# lpcdev.net
KiCad netlist of a schematic drawn in EAGLE
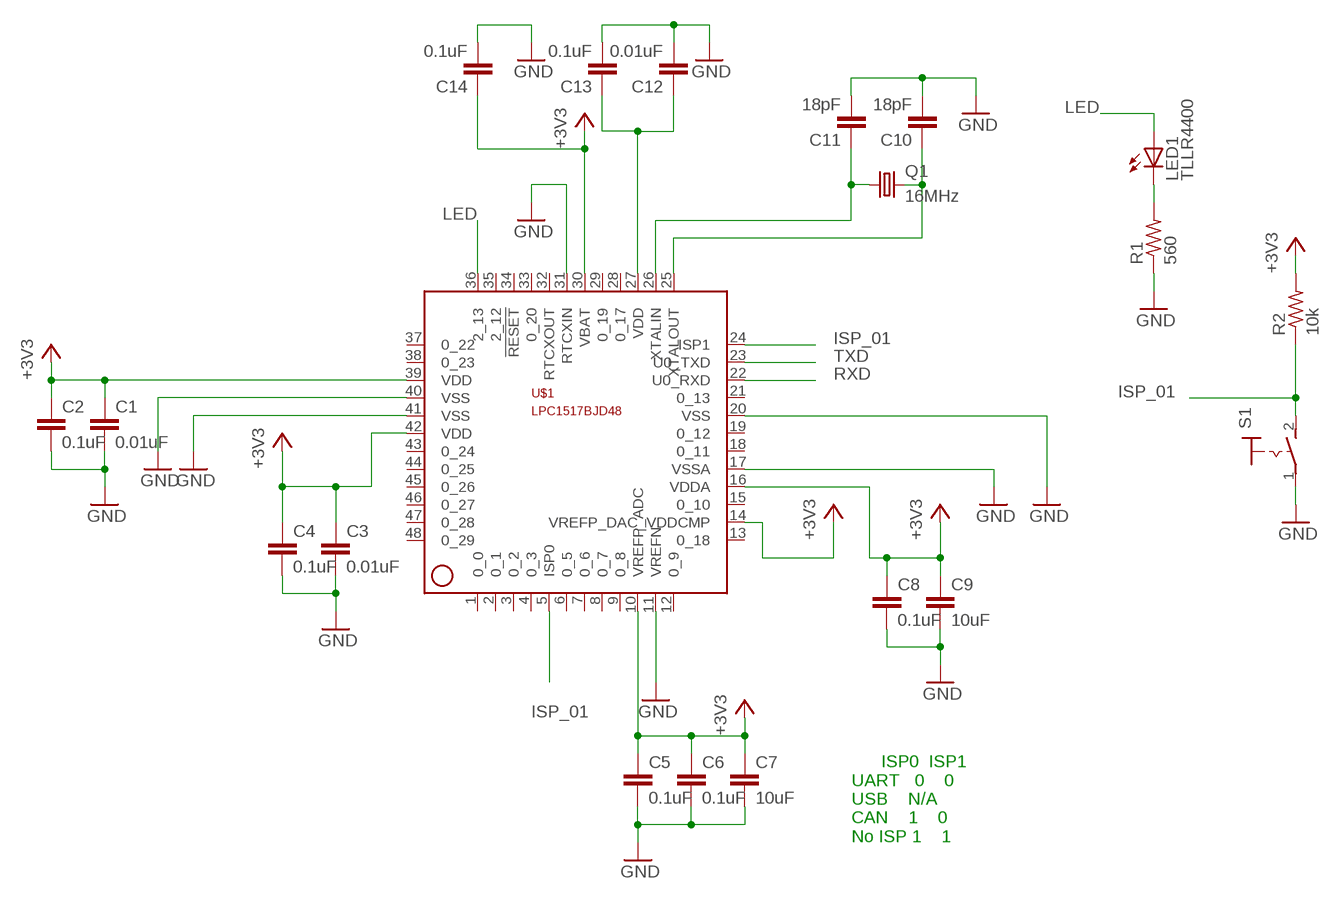
[diagram p0: schematic, sheet 1]

(export (version "E")
  (design (tool "Eeschema 10.0.6"))
  (components
    (comp (ref "C1")
      (value "0.01uF")
      (footprint "eagle-import:C0805")
      (libsource (lib "eagle-import") (part "C-EUC0805"))
    )
    (comp (ref "C2")
      (value "0.1uF")
      (footprint "eagle-import:C0805")
      (libsource (lib "eagle-import") (part "C-EUC0805"))
    )
    (comp (ref "C3")
      (value "0.01uF")
      (footprint "eagle-import:C0805")
      (libsource (lib "eagle-import") (part "C-EUC0805"))
    )
    (comp (ref "C4")
      (value "0.1uF")
      (footprint "eagle-import:C0805")
      (libsource (lib "eagle-import") (part "C-EUC0805"))
    )
    (comp (ref "C5")
      (value "0.1uF")
      (footprint "eagle-import:C0805")
      (libsource (lib "eagle-import") (part "C-EUC0805"))
    )
    (comp (ref "C6")
      (value "0.1uF")
      (footprint "eagle-import:C0805")
      (libsource (lib "eagle-import") (part "C-EUC0805"))
    )
    (comp (ref "C7")
      (value "10uF")
      (footprint "eagle-import:C0805")
      (libsource (lib "eagle-import") (part "C-EUC0805"))
    )
    (comp (ref "C8")
      (value "0.1uF")
      (footprint "eagle-import:C0805")
      (libsource (lib "eagle-import") (part "C-EUC0805"))
    )
    (comp (ref "C9")
      (value "10uF")
      (footprint "eagle-import:C0805")
      (libsource (lib "eagle-import") (part "C-EUC0805"))
    )
    (comp (ref "C10")
      (value "18pF")
      (footprint "eagle-import:C0805")
      (libsource (lib "eagle-import") (part "C-EUC0805"))
    )
    (comp (ref "C11")
      (value "18pF")
      (footprint "eagle-import:C0805")
      (libsource (lib "eagle-import") (part "C-EUC0805"))
    )
    (comp (ref "C12")
      (value "0.01uF")
      (footprint "eagle-import:C0805")
      (libsource (lib "eagle-import") (part "C-EUC0805"))
    )
    (comp (ref "C13")
      (value "0.1uF")
      (footprint "eagle-import:C0805")
      (libsource (lib "eagle-import") (part "C-EUC0805"))
    )
    (comp (ref "C14")
      (value "0.1uF")
      (footprint "eagle-import:C0805")
      (libsource (lib "eagle-import") (part "C-EUC0805"))
    )
    (comp (ref "LED1")
      (value "TLLR4400")
      (footprint "eagle-import:LED3MM")
      (fields (field (name "MF") "VISHAY SEMICONDUCTOR"))
      (libsource (lib "eagle-import") (part "TLLR4400"))
    )
    (comp (ref "Q1")
      (value "16MHz")
      (footprint "eagle-import:CTS406")
      (libsource (lib "eagle-import") (part "CRYSTALCTS406"))
    )
    (comp (ref "R1")
      (value "560")
      (footprint "eagle-import:0207_7")
      (libsource (lib "eagle-import") (part "R-US_0207/7"))
    )
    (comp (ref "R2")
      (value "10k")
      (footprint "eagle-import:0207_7")
      (libsource (lib "eagle-import") (part "R-US_0207/7"))
    )
    (comp (ref "S1")
      (value "MS243")
      (footprint "eagle-import:MS243")
      (libsource (lib "eagle-import") (part "MS243"))
    )
    (comp (ref "U$1")
      (value "LPC1517BJD48")
      (footprint "eagle-import:LQFP48")
      (libsource (lib "eagle-import") (part "LPC1517BJD48"))
    )
  )
  (nets
    (net (code "1") (name "+3V3") (class "Default")
      (node (ref "C1") (pin "1") (pinfunction "1_1") (pintype "passive"))
      (node (ref "C14") (pin "1") (pinfunction "1_1") (pintype "passive"))
      (node (ref "C2") (pin "1") (pinfunction "1_1") (pintype "passive"))
      (node (ref "C3") (pin "1") (pinfunction "1_1") (pintype "passive"))
      (node (ref "C4") (pin "1") (pinfunction "1_1") (pintype "passive"))
      (node (ref "C5") (pin "1") (pinfunction "1_1") (pintype "passive"))
      (node (ref "C6") (pin "1") (pinfunction "1_1") (pintype "passive"))
      (node (ref "C7") (pin "1") (pinfunction "1_1") (pintype "passive"))
      (node (ref "C8") (pin "1") (pinfunction "1_1") (pintype "passive"))
      (node (ref "C9") (pin "1") (pinfunction "1_1") (pintype "passive"))
      (node (ref "R2") (pin "2") (pinfunction "2_2") (pintype "passive"))
      (node (ref "U$1") (pin "10") (pinfunction "VREFP_ADC_10") (pintype "power_in"))
      (node (ref "U$1") (pin "14") (pinfunction "VREFP_DAC_VDDCMP_14") (pintype "power_in"))
      (node (ref "U$1") (pin "16") (pinfunction "VDDA_16") (pintype "power_in"))
      (node (ref "U$1") (pin "30") (pinfunction "VBAT_30") (pintype "power_in"))
      (node (ref "U$1") (pin "39") (pinfunction "VDD_39") (pintype "power_in"))
      (node (ref "U$1") (pin "42") (pinfunction "VDD_42") (pintype "power_in"))
    )
    (net (code "2") (name "/ISP_01") (class "Default")
      (node (ref "R2") (pin "1") (pinfunction "1_1") (pintype "passive"))
      (node (ref "S1") (pin "2") (pinfunction "S_2") (pintype "passive"))
      (node (ref "U$1") (pin "24") (pinfunction "ISP1_24") (pintype "bidirectional"))
      (node (ref "U$1") (pin "5") (pinfunction "ISP0_5") (pintype "bidirectional"))
    )
    (net (code "3") (name "/LED") (class "Default")
      (node (ref "LED1") (pin "A") (pinfunction "A_A") (pintype "passive"))
      (node (ref "U$1") (pin "36") (pinfunction "2_13_36") (pintype "bidirectional"))
    )
    (net (code "4") (name "/RXD") (class "Default")
      (node (ref "U$1") (pin "22") (pinfunction "U0_RXD_22") (pintype "bidirectional"))
    )
    (net (code "5") (name "/TXD") (class "Default")
      (node (ref "U$1") (pin "23") (pinfunction "U0_TXD_23") (pintype "bidirectional"))
    )
    (net (code "6") (name "GND") (class "Default")
      (node (ref "C1") (pin "2") (pinfunction "2_2") (pintype "passive"))
      (node (ref "C10") (pin "2") (pinfunction "2_2") (pintype "passive"))
      (node (ref "C11") (pin "2") (pinfunction "2_2") (pintype "passive"))
      (node (ref "C12") (pin "2") (pinfunction "2_2") (pintype "passive"))
      (node (ref "C13") (pin "2") (pinfunction "2_2") (pintype "passive"))
      (node (ref "C14") (pin "2") (pinfunction "2_2") (pintype "passive"))
      (node (ref "C2") (pin "2") (pinfunction "2_2") (pintype "passive"))
      (node (ref "C3") (pin "2") (pinfunction "2_2") (pintype "passive"))
      (node (ref "C4") (pin "2") (pinfunction "2_2") (pintype "passive"))
      (node (ref "C5") (pin "2") (pinfunction "2_2") (pintype "passive"))
      (node (ref "C6") (pin "2") (pinfunction "2_2") (pintype "passive"))
      (node (ref "C7") (pin "2") (pinfunction "2_2") (pintype "passive"))
      (node (ref "C8") (pin "2") (pinfunction "2_2") (pintype "passive"))
      (node (ref "C9") (pin "2") (pinfunction "2_2") (pintype "passive"))
      (node (ref "R1") (pin "1") (pinfunction "1_1") (pintype "passive"))
      (node (ref "S1") (pin "1") (pinfunction "P_1") (pintype "passive"))
      (node (ref "U$1") (pin "11") (pinfunction "VREFN_11") (pintype "power_in"))
      (node (ref "U$1") (pin "17") (pinfunction "VSSA_17") (pintype "power_in"))
      (node (ref "U$1") (pin "20") (pinfunction "VSS_20") (pintype "power_in"))
      (node (ref "U$1") (pin "31") (pinfunction "RTCXIN_31") (pintype "bidirectional"))
      (node (ref "U$1") (pin "40") (pinfunction "VSS_40") (pintype "power_in"))
      (node (ref "U$1") (pin "41") (pinfunction "VSS_41") (pintype "power_in"))
    )
    (net (code "7") (name "Net-(C12-Pad1)") (class "Default")
      (node (ref "C12") (pin "1") (pinfunction "1_1") (pintype "passive"))
      (node (ref "C13") (pin "1") (pinfunction "1_1") (pintype "passive"))
      (node (ref "U$1") (pin "27") (pinfunction "VDD_27") (pintype "power_in"))
    )
    (net (code "8") (name "Net-(LED1-C)") (class "Default")
      (node (ref "LED1") (pin "K") (pinfunction "C_K") (pintype "passive"))
      (node (ref "R1") (pin "2") (pinfunction "2_2") (pintype "passive"))
    )
    (net (code "9") (name "Net-(Q1-2)") (class "Default")
      (node (ref "C10") (pin "1") (pinfunction "1_1") (pintype "passive"))
      (node (ref "Q1") (pin "3") (pinfunction "2_3") (pintype "passive"))
      (node (ref "U$1") (pin "25") (pinfunction "XTALOUT_25") (pintype "bidirectional"))
    )
    (net (code "10") (name "Net-(U$1-XTALIN)") (class "Default")
      (node (ref "C11") (pin "1") (pinfunction "1_1") (pintype "passive"))
      (node (ref "Q1") (pin "1") (pinfunction "1_1") (pintype "passive"))
      (node (ref "U$1") (pin "26") (pinfunction "XTALIN_26") (pintype "bidirectional"))
    )
    (net (code "11") (name "unconnected-(U$1-0_0-Pad1)") (class "Default")
      (node (ref "U$1") (pin "1") (pinfunction "0_0_1") (pintype "bidirectional"))
    )
    (net (code "12") (name "unconnected-(U$1-0_1-Pad2)") (class "Default")
      (node (ref "U$1") (pin "2") (pinfunction "0_1_2") (pintype "bidirectional"))
    )
    (net (code "13") (name "unconnected-(U$1-0_2-Pad3)") (class "Default")
      (node (ref "U$1") (pin "3") (pinfunction "0_2_3") (pintype "bidirectional"))
    )
    (net (code "14") (name "unconnected-(U$1-0_3-Pad4)") (class "Default")
      (node (ref "U$1") (pin "4") (pinfunction "0_3_4") (pintype "bidirectional"))
    )
    (net (code "15") (name "unconnected-(U$1-0_5-Pad6)") (class "Default")
      (node (ref "U$1") (pin "6") (pinfunction "0_5_6") (pintype "bidirectional"))
    )
    (net (code "16") (name "unconnected-(U$1-0_6-Pad7)") (class "Default")
      (node (ref "U$1") (pin "7") (pinfunction "0_6_7") (pintype "bidirectional"))
    )
    (net (code "17") (name "unconnected-(U$1-0_7-Pad8)") (class "Default")
      (node (ref "U$1") (pin "8") (pinfunction "0_7_8") (pintype "bidirectional"))
    )
    (net (code "18") (name "unconnected-(U$1-0_8-Pad9)") (class "Default")
      (node (ref "U$1") (pin "9") (pinfunction "0_8_9") (pintype "bidirectional"))
    )
    (net (code "19") (name "unconnected-(U$1-0_9-Pad12)") (class "Default")
      (node (ref "U$1") (pin "12") (pinfunction "0_9_12") (pintype "bidirectional"))
    )
    (net (code "20") (name "unconnected-(U$1-0_10-Pad15)") (class "Default")
      (node (ref "U$1") (pin "15") (pinfunction "0_10_15") (pintype "bidirectional"))
    )
    (net (code "21") (name "unconnected-(U$1-0_11-Pad18)") (class "Default")
      (node (ref "U$1") (pin "18") (pinfunction "0_11_18") (pintype "bidirectional"))
    )
    (net (code "22") (name "unconnected-(U$1-0_12-Pad19)") (class "Default")
      (node (ref "U$1") (pin "19") (pinfunction "0_12_19") (pintype "bidirectional"))
    )
    (net (code "23") (name "unconnected-(U$1-0_13-Pad21)") (class "Default")
      (node (ref "U$1") (pin "21") (pinfunction "0_13_21") (pintype "bidirectional"))
    )
    (net (code "24") (name "unconnected-(U$1-0_17-Pad28)") (class "Default")
      (node (ref "U$1") (pin "28") (pinfunction "0_17_28") (pintype "bidirectional"))
    )
    (net (code "25") (name "unconnected-(U$1-0_18-Pad13)") (class "Default")
      (node (ref "U$1") (pin "13") (pinfunction "0_18_13") (pintype "bidirectional"))
    )
    (net (code "26") (name "unconnected-(U$1-0_19-Pad29)") (class "Default")
      (node (ref "U$1") (pin "29") (pinfunction "0_19_29") (pintype "bidirectional"))
    )
    (net (code "27") (name "unconnected-(U$1-0_20-Pad33)") (class "Default")
      (node (ref "U$1") (pin "33") (pinfunction "0_20_33") (pintype "bidirectional"))
    )
    (net (code "28") (name "unconnected-(U$1-0_22-Pad37)") (class "Default")
      (node (ref "U$1") (pin "37") (pinfunction "0_22_37") (pintype "bidirectional"))
    )
    (net (code "29") (name "unconnected-(U$1-0_23-Pad38)") (class "Default")
      (node (ref "U$1") (pin "38") (pinfunction "0_23_38") (pintype "bidirectional"))
    )
    (net (code "30") (name "unconnected-(U$1-0_24-Pad43)") (class "Default")
      (node (ref "U$1") (pin "43") (pinfunction "0_24_43") (pintype "bidirectional"))
    )
    (net (code "31") (name "unconnected-(U$1-0_25-Pad44)") (class "Default")
      (node (ref "U$1") (pin "44") (pinfunction "0_25_44") (pintype "bidirectional"))
    )
    (net (code "32") (name "unconnected-(U$1-0_26-Pad45)") (class "Default")
      (node (ref "U$1") (pin "45") (pinfunction "0_26_45") (pintype "bidirectional"))
    )
    (net (code "33") (name "unconnected-(U$1-0_27-Pad46)") (class "Default")
      (node (ref "U$1") (pin "46") (pinfunction "0_27_46") (pintype "bidirectional"))
    )
    (net (code "34") (name "unconnected-(U$1-0_28-Pad47)") (class "Default")
      (node (ref "U$1") (pin "47") (pinfunction "0_28_47") (pintype "bidirectional"))
    )
    (net (code "35") (name "unconnected-(U$1-0_29-Pad48)") (class "Default")
      (node (ref "U$1") (pin "48") (pinfunction "0_29_48") (pintype "bidirectional"))
    )
    (net (code "36") (name "unconnected-(U$1-2_12-Pad35)") (class "Default")
      (node (ref "U$1") (pin "35") (pinfunction "2_12_35") (pintype "bidirectional"))
    )
    (net (code "37") (name "unconnected-(U$1-RTCXOUT-Pad32)") (class "Default")
      (node (ref "U$1") (pin "32") (pinfunction "RTCXOUT_32") (pintype "bidirectional"))
    )
    (net (code "38") (name "unconnected-(U$1-~{RESET}-Pad34)") (class "Default")
      (node (ref "U$1") (pin "34") (pinfunction "~{RESET}_34") (pintype "bidirectional"))
    )
  )
)
